# -_-20240226.net
KiCad netlist of a schematic drawn in EasyEDA Pro
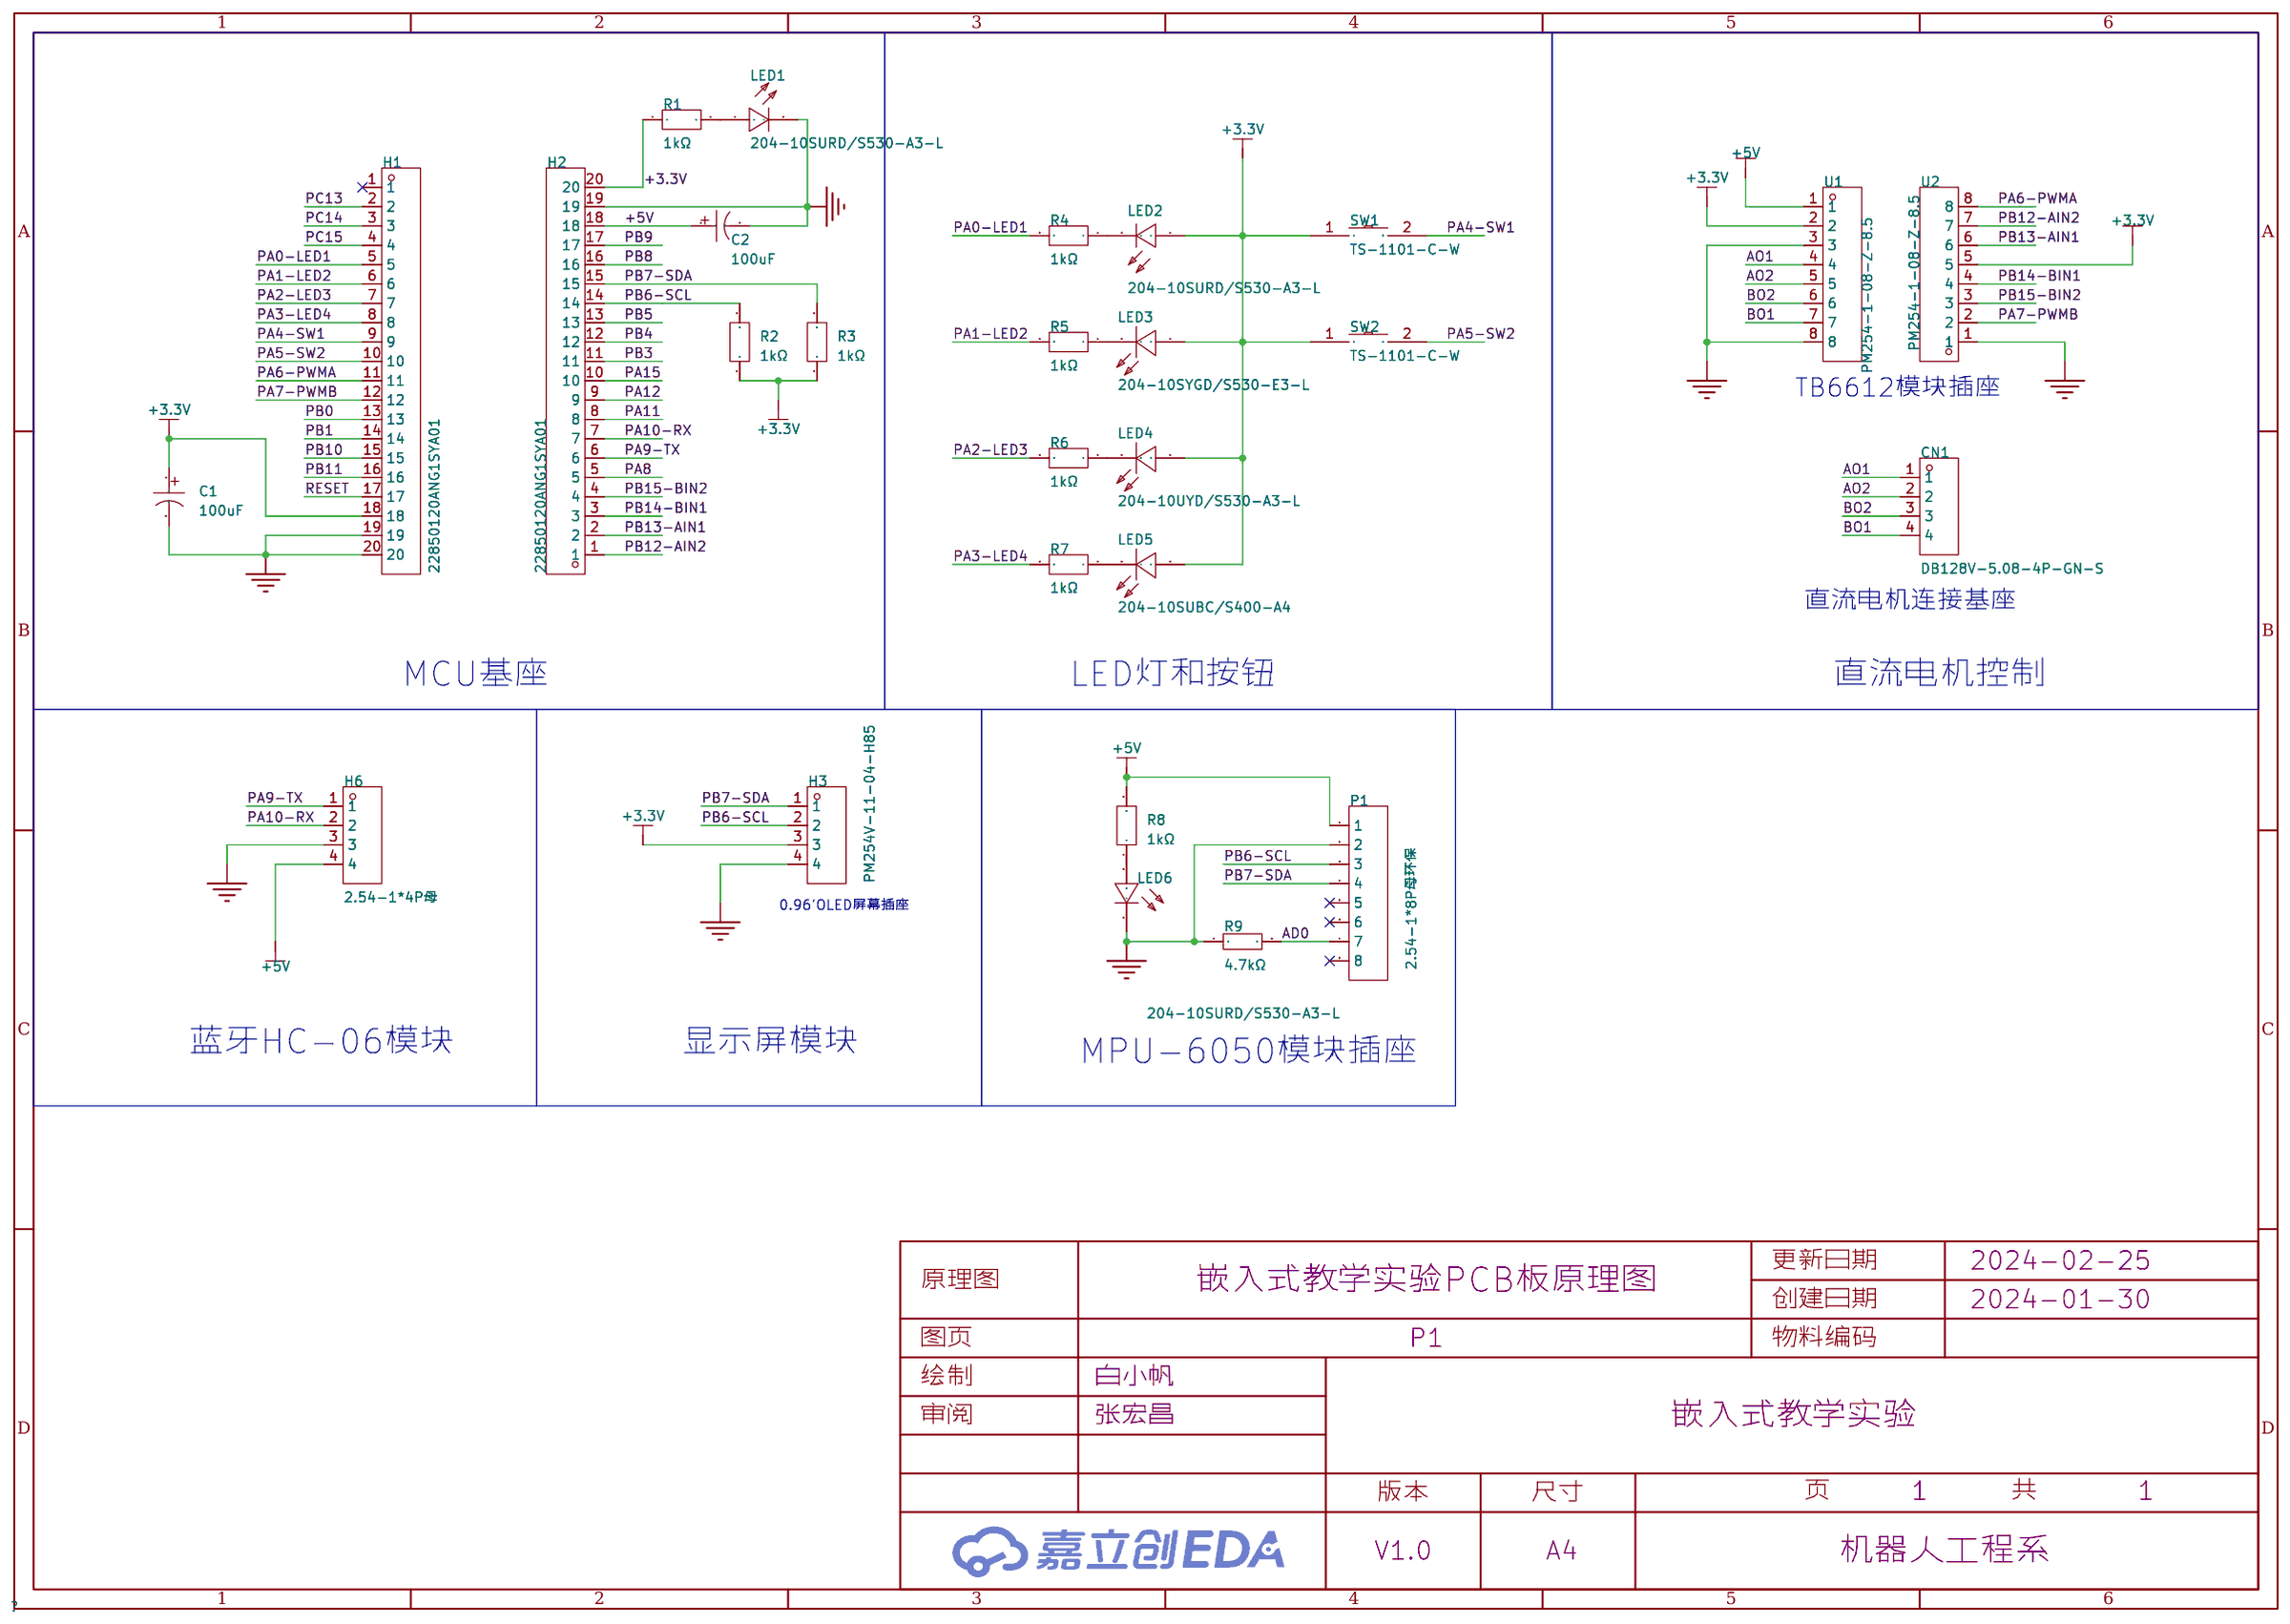
[diagram p0: schematic sheet]

(export (version "E")
  (design (tool "Eeschema 10.0.6"))
  (components
    (comp (ref "C1")
      (value "100uF")
      (footprint "easyedapro:CAP-TH_BD8.0-P3.50-D0.6-FD")
      (description "容值:100uF;精度:±20%;额定电压:50V;")
      (fields (field (name "Manufacturer Part") "ERS1HM101F12OT") (field (name "Manufacturer") "AISHI(艾华集团)"))
      (libsource (lib "easyedapro") (part "ERS1HM101F12OT"))
    )
    (comp (ref "C2")
      (value "100uF")
      (footprint "easyedapro:CAP-TH_BD8.0-P3.50-D0.6-FD")
      (description "容值:100uF;精度:±20%;额定电压:50V;")
      (fields (field (name "Manufacturer Part") "ERS1HM101F12OT") (field (name "Manufacturer") "AISHI(艾华集团)"))
      (libsource (lib "easyedapro") (part "ERS1HM101F12OT"))
    )
    (comp (ref "CN1")
      (value "DB128V-5.08-4P-GN-S")
      (footprint "easyedapro:CONN-TH_4P-P5.08_DIBO_DB128V-5.08")
      (fields (field (name "Manufacturer") "DORABO(地博电气)"))
      (libsource (lib "easyedapro") (part "DB128V-5.08-4P-GN-S"))
    )
    (comp (ref "H1")
      (value "22850120ANG1SYA01")
      (footprint "easyedapro:HDR-TH_20P-P2.54-V-F")
      (description "排数:单排;总孔位数:20P;间距:2.54mm;插孔结构:1x20P;行距:-;安装类型:直插;塑高:-;触头材质:黄铜;触头镀层:-;")
      (fields (field (name "Manufacturer") "JILN(锦凌)"))
      (libsource (lib "easyedapro") (part "22850120ANG1SYA01"))
    )
    (comp (ref "H2")
      (value "22850120ANG1SYA01")
      (footprint "easyedapro:HDR-TH_20P-P2.54-V-F")
      (description "排数:单排;总孔位数:20P;间距:2.54mm;插孔结构:1x20P;行距:-;安装类型:直插;塑高:-;触头材质:黄铜;触头镀层:-;")
      (fields (field (name "Manufacturer") "JILN(锦凌)"))
      (libsource (lib "easyedapro") (part "22850120ANG1SYA01"))
    )
    (comp (ref "H3")
      (value "PM254V-11-04-H85")
      (footprint "easyedapro:HDR-TH_4P-P2.54-V-F")
      (description "插孔结构:1x4P;间距:2.54mm;行距:-;安装类型:直插;排数:单排;总孔位数:4P;塑高:-;触头材质:黄铜;触头镀层:-;")
      (fields (field (name "Manufacturer") "XFCN(兴飞)"))
      (libsource (lib "easyedapro") (part "PM254V-11-04-H85"))
    )
    (comp (ref "H6")
      (value "2.54-1*4P母")
      (footprint "easyedapro:HDR-TH_4P-P2.54-V-F")
      (fields (field (name "Manufacturer") "BOOMELE(博穆精密)"))
      (libsource (lib "easyedapro") (part "2.54-1*4P母"))
    )
    (comp (ref "LED1")
      (value "204-10SURD/S530-A3-L")
      (footprint "easyedapro:LED-TH_BD3.0-P2.54-FD")
      (fields (field (name "Manufacturer") "EVERLIGHT(亿光)"))
      (libsource (lib "easyedapro") (part "204-10SURD/S530-A3-L"))
    )
    (comp (ref "LED2")
      (value "204-10SURD/S530-A3-L")
      (footprint "easyedapro:LED-TH_BD3.0-P2.54-FD")
      (fields (field (name "Manufacturer") "EVERLIGHT(亿光)"))
      (libsource (lib "easyedapro") (part "204-10SURD/S530-A3-L"))
    )
    (comp (ref "LED3")
      (value "204-10SYGD/S530-E3-L")
      (footprint "easyedapro:LED-TH_BD3.0-P2.54-FD")
      (description "灯头类型:3mm圆形灯头;发光颜色:黄绿色;")
      (fields (field (name "Manufacturer") "EVERLIGHT(亿光)"))
      (libsource (lib "easyedapro") (part "204-10SYGD/S530-E3-L"))
    )
    (comp (ref "LED4")
      (value "204-10UYD/S530-A3-L")
      (footprint "easyedapro:LED-TH_BD3.0-P2.54-FD")
      (description "灯头类型:3mm圆形灯头;发光颜色:黄色;")
      (fields (field (name "Manufacturer") "EVERLIGHT(亿光)"))
      (libsource (lib "easyedapro") (part "204-10UYD/S530-A3-L"))
    )
    (comp (ref "LED5")
      (value "204-10SUBC/S400-A4")
      (footprint "easyedapro:LED-TH_BD4.0-P2.54-FD")
      (description "灯头类型:3mm圆形灯头;发光颜色:蓝色;")
      (fields (field (name "Manufacturer") "EVERLIGHT(亿光)"))
      (libsource (lib "easyedapro") (part "204-10SUBC/S400-A4"))
    )
    (comp (ref "LED6")
      (value "204-10SURD/S530-A3-L")
      (footprint "easyedapro:LED-TH_BD3.0-P2.54-FD")
      (fields (field (name "Manufacturer") "EVERLIGHT(亿光)"))
      (libsource (lib "easyedapro") (part "204-10SURD/S530-A3-L"))
    )
    (comp (ref "P1")
      (value "2.54-1*8P母环保")
      (footprint "easyedapro:HDR-TH_8P-P2.54-V-F-1")
      (description "排数:单排;总孔位数:8P;间距:2.54mm;插孔结构:1x8P;行距:-;安装类型:直插;塑高:-;触头材质:-;触头镀层:-;")
      (fields (field (name "Manufacturer") "BOOMELE(博穆精密)"))
      (libsource (lib "easyedapro") (part "Header-Female-2.54_1x8"))
    )
    (comp (ref "R1")
      (value "1kΩ")
      (footprint "easyedapro:RES-TH_BD2.3-L6.5-P10.50-D0.5")
      (description "电阻类型:金属膜电阻;阻值:1kΩ;精度:±1%;功率:250mW;温度系数:±200ppm/°C;")
      (fields (field (name "Manufacturer Part") "MF1/4W-1KΩ±1%T52") (field (name "Manufacturer") "华星机电"))
      (libsource (lib "easyedapro") (part "MF1/4W-1KΩ±1%T52"))
    )
    (comp (ref "R2")
      (value "1kΩ")
      (footprint "easyedapro:RES-TH_BD2.3-L6.5-P10.50-D0.5")
      (description "电阻类型:金属膜电阻;阻值:1kΩ;精度:±1%;功率:250mW;温度系数:±200ppm/°C;")
      (fields (field (name "Manufacturer Part") "MF1/4W-1KΩ±1%T52") (field (name "Manufacturer") "华星机电"))
      (libsource (lib "easyedapro") (part "MF1/4W-1KΩ±1%T52"))
    )
    (comp (ref "R3")
      (value "1kΩ")
      (footprint "easyedapro:RES-TH_BD2.3-L6.5-P10.50-D0.5")
      (description "电阻类型:金属膜电阻;阻值:1kΩ;精度:±1%;功率:250mW;温度系数:±200ppm/°C;")
      (fields (field (name "Manufacturer Part") "MF1/4W-1KΩ±1%T52") (field (name "Manufacturer") "华星机电"))
      (libsource (lib "easyedapro") (part "MF1/4W-1KΩ±1%T52"))
    )
    (comp (ref "R4")
      (value "1kΩ")
      (footprint "easyedapro:RES-TH_BD2.3-L6.5-P10.50-D0.5")
      (description "电阻类型:金属膜电阻;阻值:1kΩ;精度:±1%;功率:250mW;温度系数:±200ppm/°C;")
      (fields (field (name "Manufacturer Part") "MF1/4W-1KΩ±1%T52") (field (name "Manufacturer") "华星机电"))
      (libsource (lib "easyedapro") (part "MF1/4W-1KΩ±1%T52"))
    )
    (comp (ref "R5")
      (value "1kΩ")
      (footprint "easyedapro:RES-TH_BD2.3-L6.5-P10.50-D0.5")
      (description "电阻类型:金属膜电阻;阻值:1kΩ;精度:±1%;功率:250mW;温度系数:±200ppm/°C;")
      (fields (field (name "Manufacturer Part") "MF1/4W-1KΩ±1%T52") (field (name "Manufacturer") "华星机电"))
      (libsource (lib "easyedapro") (part "MF1/4W-1KΩ±1%T52"))
    )
    (comp (ref "R6")
      (value "1kΩ")
      (footprint "easyedapro:RES-TH_BD2.3-L6.5-P10.50-D0.5")
      (description "电阻类型:金属膜电阻;阻值:1kΩ;精度:±1%;功率:250mW;温度系数:±200ppm/°C;")
      (fields (field (name "Manufacturer Part") "MF1/4W-1KΩ±1%T52") (field (name "Manufacturer") "华星机电"))
      (libsource (lib "easyedapro") (part "MF1/4W-1KΩ±1%T52"))
    )
    (comp (ref "R7")
      (value "1kΩ")
      (footprint "easyedapro:RES-TH_BD2.3-L6.5-P10.50-D0.5")
      (description "电阻类型:金属膜电阻;阻值:1kΩ;精度:±1%;功率:250mW;温度系数:±200ppm/°C;")
      (fields (field (name "Manufacturer Part") "MF1/4W-1KΩ±1%T52") (field (name "Manufacturer") "华星机电"))
      (libsource (lib "easyedapro") (part "MF1/4W-1KΩ±1%T52"))
    )
    (comp (ref "R8")
      (value "1kΩ")
      (footprint "easyedapro:RES-TH_BD2.3-L6.5-P10.50-D0.5")
      (description "电阻类型:金属膜电阻;阻值:1kΩ;精度:±1%;功率:250mW;温度系数:±200ppm/°C;")
      (fields (field (name "Manufacturer Part") "MF1/4W-1KΩ±1%T52") (field (name "Manufacturer") "华星机电"))
      (libsource (lib "easyedapro") (part "MF1/4W-1KΩ±1%T52"))
    )
    (comp (ref "R9")
      (value "4.7kΩ")
      (footprint "easyedapro:RES-TH_BD2.3-L6.5-P10.50-D0.5")
      (description "电阻类型:金属膜电阻;阻值:4.7kΩ;精度:±1%;功率:250mW;温度系数:±100ppm/°C;")
      (fields
        (field (name "Manufacturer Part") "MF1/4W-4.7KΩ±1% T")
        (field (name "Manufacturer") "CCO(千志电子)")
      )
      (libsource (lib "easyedapro") (part "MF1/4W-4.7KΩ±1% T52"))
    )
    (comp (ref "SW1")
      (value "TS-1101-C-W")
      (footprint "easyedapro:SW-SMD_L6.0-W3.3-LS8.0")
      (fields (field (name "Manufacturer") "XKB Connectivity(中国星坤)"))
      (libsource (lib "easyedapro") (part "TS-1101-C-W"))
    )
    (comp (ref "SW2")
      (value "TS-1101-C-W")
      (footprint "easyedapro:SW-SMD_L6.0-W3.3-LS8.0")
      (fields (field (name "Manufacturer") "XKB Connectivity(中国星坤)"))
      (libsource (lib "easyedapro") (part "TS-1101-C-W"))
    )
    (comp (ref "U1")
      (value "PM254-1-08-Z-8.5")
      (footprint "easyedapro:HDR-TH_8P-P2.54-V-F")
      (fields (field (name "Manufacturer") "HCTL(华灿天禄)"))
      (libsource (lib "easyedapro") (part "PM254-1-08-Z-8.5"))
    )
    (comp (ref "U2")
      (value "PM254-1-08-Z-8.5")
      (footprint "easyedapro:HDR-TH_8P-P2.54-V-F")
      (fields (field (name "Manufacturer") "HCTL(华灿天禄)"))
      (libsource (lib "easyedapro") (part "PM254-1-08-Z-8.5"))
    )
  )
  (nets
    (net (code "1") (name "+3.3V") (class "Default")
      (node (ref "C1") (pin "1") (pinfunction "1_1") (pintype "input"))
      (node (ref "H1") (pin "18") (pinfunction "18_18") (pintype "unspecified"))
      (node (ref "H2") (pin "20") (pinfunction "20_20") (pintype "unspecified"))
      (node (ref "H3") (pin "3") (pinfunction "3_3") (pintype "unspecified"))
      (node (ref "LED2") (pin "1") (pinfunction "A_1") (pintype "input"))
      (node (ref "LED3") (pin "1") (pinfunction "A_1") (pintype "unspecified"))
      (node (ref "LED4") (pin "1") (pinfunction "A_1") (pintype "unspecified"))
      (node (ref "LED5") (pin "1") (pinfunction "+_1") (pintype "unspecified"))
      (node (ref "R1") (pin "1") (pinfunction "1_1") (pintype "unspecified"))
      (node (ref "R2") (pin "1") (pinfunction "1_1") (pintype "unspecified"))
      (node (ref "R3") (pin "1") (pinfunction "1_1") (pintype "unspecified"))
      (node (ref "SW1") (pin "1") (pinfunction "1_1") (pintype "unspecified"))
      (node (ref "SW2") (pin "1") (pinfunction "1_1") (pintype "unspecified"))
      (node (ref "U1") (pin "2") (pinfunction "2_2") (pintype "unspecified"))
      (node (ref "U2") (pin "5") (pinfunction "5_5") (pintype "unspecified"))
    )
    (net (code "2") (name "+5V") (class "Default")
      (node (ref "C2") (pin "1") (pinfunction "1_1") (pintype "input"))
      (node (ref "H2") (pin "18") (pinfunction "18_18") (pintype "unspecified"))
      (node (ref "H6") (pin "4") (pinfunction "4_4") (pintype "unspecified"))
      (node (ref "P1") (pin "1") (pinfunction "1_1") (pintype "input"))
      (node (ref "R8") (pin "2") (pinfunction "2_2") (pintype "unspecified"))
      (node (ref "U1") (pin "1") (pinfunction "1_1") (pintype "unspecified"))
    )
    (net (code "3") (name "/AD0") (class "Default")
      (node (ref "P1") (pin "7") (pinfunction "7_7") (pintype "input"))
      (node (ref "R9") (pin "2") (pinfunction "2_2") (pintype "unspecified"))
    )
    (net (code "4") (name "/AO1") (class "Default")
      (node (ref "CN1") (pin "1") (pinfunction "1_1") (pintype "unspecified"))
      (node (ref "U1") (pin "4") (pinfunction "4_4") (pintype "unspecified"))
    )
    (net (code "5") (name "/AO2") (class "Default")
      (node (ref "CN1") (pin "2") (pinfunction "2_2") (pintype "unspecified"))
      (node (ref "U1") (pin "5") (pinfunction "5_5") (pintype "unspecified"))
    )
    (net (code "6") (name "/BO1") (class "Default")
      (node (ref "CN1") (pin "4") (pinfunction "4_4") (pintype "unspecified"))
      (node (ref "U1") (pin "7") (pinfunction "7_7") (pintype "unspecified"))
    )
    (net (code "7") (name "/BO2") (class "Default")
      (node (ref "CN1") (pin "3") (pinfunction "3_3") (pintype "unspecified"))
      (node (ref "U1") (pin "6") (pinfunction "6_6") (pintype "unspecified"))
    )
    (net (code "8") (name "/PA0-LED1") (class "Default")
      (node (ref "H1") (pin "5") (pinfunction "5_5") (pintype "unspecified"))
      (node (ref "R4") (pin "2") (pinfunction "2_2") (pintype "unspecified"))
    )
    (net (code "9") (name "/PA1-LED2") (class "Default")
      (node (ref "H1") (pin "6") (pinfunction "6_6") (pintype "unspecified"))
      (node (ref "R5") (pin "2") (pinfunction "2_2") (pintype "unspecified"))
    )
    (net (code "10") (name "/PA2-LED3") (class "Default")
      (node (ref "H1") (pin "7") (pinfunction "7_7") (pintype "unspecified"))
      (node (ref "R6") (pin "2") (pinfunction "2_2") (pintype "unspecified"))
    )
    (net (code "11") (name "/PA3-LED4") (class "Default")
      (node (ref "H1") (pin "8") (pinfunction "8_8") (pintype "unspecified"))
      (node (ref "R7") (pin "2") (pinfunction "2_2") (pintype "unspecified"))
    )
    (net (code "12") (name "/PA4-SW1") (class "Default")
      (node (ref "H1") (pin "9") (pinfunction "9_9") (pintype "unspecified"))
      (node (ref "SW1") (pin "2") (pinfunction "2_2") (pintype "unspecified"))
    )
    (net (code "13") (name "/PA5-SW2") (class "Default")
      (node (ref "H1") (pin "10") (pinfunction "10_10") (pintype "unspecified"))
      (node (ref "SW2") (pin "2") (pinfunction "2_2") (pintype "unspecified"))
    )
    (net (code "14") (name "/PA6-PWMA") (class "Default")
      (node (ref "H1") (pin "11") (pinfunction "11_11") (pintype "unspecified"))
      (node (ref "U2") (pin "8") (pinfunction "8_8") (pintype "unspecified"))
    )
    (net (code "15") (name "/PA7-PWMB") (class "Default")
      (node (ref "H1") (pin "12") (pinfunction "12_12") (pintype "unspecified"))
      (node (ref "U2") (pin "2") (pinfunction "2_2") (pintype "unspecified"))
    )
    (net (code "16") (name "/PA8") (class "Default")
      (node (ref "H2") (pin "5") (pinfunction "5_5") (pintype "unspecified"))
    )
    (net (code "17") (name "/PA9-TX") (class "Default")
      (node (ref "H2") (pin "6") (pinfunction "6_6") (pintype "unspecified"))
      (node (ref "H6") (pin "1") (pinfunction "1_1") (pintype "unspecified"))
    )
    (net (code "18") (name "/PA10-RX") (class "Default")
      (node (ref "H2") (pin "7") (pinfunction "7_7") (pintype "unspecified"))
      (node (ref "H6") (pin "2") (pinfunction "2_2") (pintype "unspecified"))
    )
    (net (code "19") (name "/PA11") (class "Default")
      (node (ref "H2") (pin "8") (pinfunction "8_8") (pintype "unspecified"))
    )
    (net (code "20") (name "/PA12") (class "Default")
      (node (ref "H2") (pin "9") (pinfunction "9_9") (pintype "unspecified"))
    )
    (net (code "21") (name "/PA15") (class "Default")
      (node (ref "H2") (pin "10") (pinfunction "10_10") (pintype "unspecified"))
    )
    (net (code "22") (name "/PB0") (class "Default")
      (node (ref "H1") (pin "13") (pinfunction "13_13") (pintype "unspecified"))
    )
    (net (code "23") (name "/PB1") (class "Default")
      (node (ref "H1") (pin "14") (pinfunction "14_14") (pintype "unspecified"))
    )
    (net (code "24") (name "/PB3") (class "Default")
      (node (ref "H2") (pin "11") (pinfunction "11_11") (pintype "unspecified"))
    )
    (net (code "25") (name "/PB4") (class "Default")
      (node (ref "H2") (pin "12") (pinfunction "12_12") (pintype "unspecified"))
    )
    (net (code "26") (name "/PB5") (class "Default")
      (node (ref "H2") (pin "13") (pinfunction "13_13") (pintype "unspecified"))
    )
    (net (code "27") (name "/PB6-SCL") (class "Default")
      (node (ref "H2") (pin "14") (pinfunction "14_14") (pintype "unspecified"))
      (node (ref "H3") (pin "2") (pinfunction "2_2") (pintype "unspecified"))
      (node (ref "P1") (pin "3") (pinfunction "3_3") (pintype "input"))
      (node (ref "R2") (pin "2") (pinfunction "2_2") (pintype "unspecified"))
    )
    (net (code "28") (name "/PB7-SDA") (class "Default")
      (node (ref "H2") (pin "15") (pinfunction "15_15") (pintype "unspecified"))
      (node (ref "H3") (pin "1") (pinfunction "1_1") (pintype "unspecified"))
      (node (ref "P1") (pin "4") (pinfunction "4_4") (pintype "input"))
      (node (ref "R3") (pin "2") (pinfunction "2_2") (pintype "unspecified"))
    )
    (net (code "29") (name "/PB8") (class "Default")
      (node (ref "H2") (pin "16") (pinfunction "16_16") (pintype "unspecified"))
    )
    (net (code "30") (name "/PB9") (class "Default")
      (node (ref "H2") (pin "17") (pinfunction "17_17") (pintype "unspecified"))
    )
    (net (code "31") (name "/PB10") (class "Default")
      (node (ref "H1") (pin "15") (pinfunction "15_15") (pintype "unspecified"))
    )
    (net (code "32") (name "/PB11") (class "Default")
      (node (ref "H1") (pin "16") (pinfunction "16_16") (pintype "unspecified"))
    )
    (net (code "33") (name "/PB12-AIN2") (class "Default")
      (node (ref "H2") (pin "1") (pinfunction "1_1") (pintype "unspecified"))
      (node (ref "U2") (pin "7") (pinfunction "7_7") (pintype "unspecified"))
    )
    (net (code "34") (name "/PB13-AIN1") (class "Default")
      (node (ref "H2") (pin "2") (pinfunction "2_2") (pintype "unspecified"))
      (node (ref "U2") (pin "6") (pinfunction "6_6") (pintype "unspecified"))
    )
    (net (code "35") (name "/PB14-BIN1") (class "Default")
      (node (ref "H2") (pin "3") (pinfunction "3_3") (pintype "unspecified"))
      (node (ref "U2") (pin "4") (pinfunction "4_4") (pintype "unspecified"))
    )
    (net (code "36") (name "/PB15-BIN2") (class "Default")
      (node (ref "H2") (pin "4") (pinfunction "4_4") (pintype "unspecified"))
      (node (ref "U2") (pin "3") (pinfunction "3_3") (pintype "unspecified"))
    )
    (net (code "37") (name "/PC13") (class "Default")
      (node (ref "H1") (pin "2") (pinfunction "2_2") (pintype "unspecified"))
    )
    (net (code "38") (name "/PC14") (class "Default")
      (node (ref "H1") (pin "3") (pinfunction "3_3") (pintype "unspecified"))
    )
    (net (code "39") (name "/PC15") (class "Default")
      (node (ref "H1") (pin "4") (pinfunction "4_4") (pintype "unspecified"))
    )
    (net (code "40") (name "/RESET") (class "Default")
      (node (ref "H1") (pin "17") (pinfunction "17_17") (pintype "unspecified"))
    )
    (net (code "41") (name "GND") (class "Default")
      (node (ref "C1") (pin "2") (pinfunction "2_2") (pintype "input"))
      (node (ref "C2") (pin "2") (pinfunction "2_2") (pintype "input"))
      (node (ref "H1") (pin "19") (pinfunction "19_19") (pintype "unspecified"))
      (node (ref "H1") (pin "20") (pinfunction "20_20") (pintype "unspecified"))
      (node (ref "H2") (pin "19") (pinfunction "19_19") (pintype "unspecified"))
      (node (ref "H3") (pin "4") (pinfunction "4_4") (pintype "unspecified"))
      (node (ref "H6") (pin "3") (pinfunction "3_3") (pintype "unspecified"))
      (node (ref "LED1") (pin "2") (pinfunction "K_2") (pintype "input"))
      (node (ref "LED6") (pin "2") (pinfunction "K_2") (pintype "input"))
      (node (ref "P1") (pin "2") (pinfunction "2_2") (pintype "input"))
      (node (ref "R9") (pin "1") (pinfunction "1_1") (pintype "unspecified"))
      (node (ref "U1") (pin "3") (pinfunction "3_3") (pintype "unspecified"))
      (node (ref "U1") (pin "8") (pinfunction "8_8") (pintype "unspecified"))
      (node (ref "U2") (pin "1") (pinfunction "1_1") (pintype "unspecified"))
    )
    (net (code "42") (name "Net-(LED1-A)") (class "Default")
      (node (ref "LED1") (pin "1") (pinfunction "A_1") (pintype "input"))
      (node (ref "R1") (pin "2") (pinfunction "2_2") (pintype "unspecified"))
    )
    (net (code "43") (name "Net-(LED2-K)") (class "Default")
      (node (ref "LED2") (pin "2") (pinfunction "K_2") (pintype "input"))
      (node (ref "R4") (pin "1") (pinfunction "1_1") (pintype "unspecified"))
    )
    (net (code "44") (name "Net-(LED3-K)") (class "Default")
      (node (ref "LED3") (pin "2") (pinfunction "K_2") (pintype "unspecified"))
      (node (ref "R5") (pin "1") (pinfunction "1_1") (pintype "unspecified"))
    )
    (net (code "45") (name "Net-(LED4-K)") (class "Default")
      (node (ref "LED4") (pin "2") (pinfunction "K_2") (pintype "unspecified"))
      (node (ref "R6") (pin "1") (pinfunction "1_1") (pintype "unspecified"))
    )
    (net (code "46") (name "Net-(LED5--)") (class "Default")
      (node (ref "LED5") (pin "2") (pinfunction "-_2") (pintype "unspecified"))
      (node (ref "R7") (pin "1") (pinfunction "1_1") (pintype "unspecified"))
    )
    (net (code "47") (name "Net-(LED6-A)") (class "Default")
      (node (ref "LED6") (pin "1") (pinfunction "A_1") (pintype "input"))
      (node (ref "R8") (pin "1") (pinfunction "1_1") (pintype "unspecified"))
    )
    (net (code "48") (name "unconnected-(H1-Pad1)") (class "Default")
      (node (ref "H1") (pin "1") (pinfunction "1_1") (pintype "unspecified+no_connect"))
    )
    (net (code "49") (name "unconnected-(P1-Pad5)") (class "Default")
      (node (ref "P1") (pin "5") (pinfunction "5_5") (pintype "input+no_connect"))
    )
    (net (code "50") (name "unconnected-(P1-Pad6)") (class "Default")
      (node (ref "P1") (pin "6") (pinfunction "6_6") (pintype "input+no_connect"))
    )
    (net (code "51") (name "unconnected-(P1-Pad8)") (class "Default")
      (node (ref "P1") (pin "8") (pinfunction "8_8") (pintype "input+no_connect"))
    )
  )
)
